# controler.net
KiCad netlist of a schematic drawn in Altium Designer
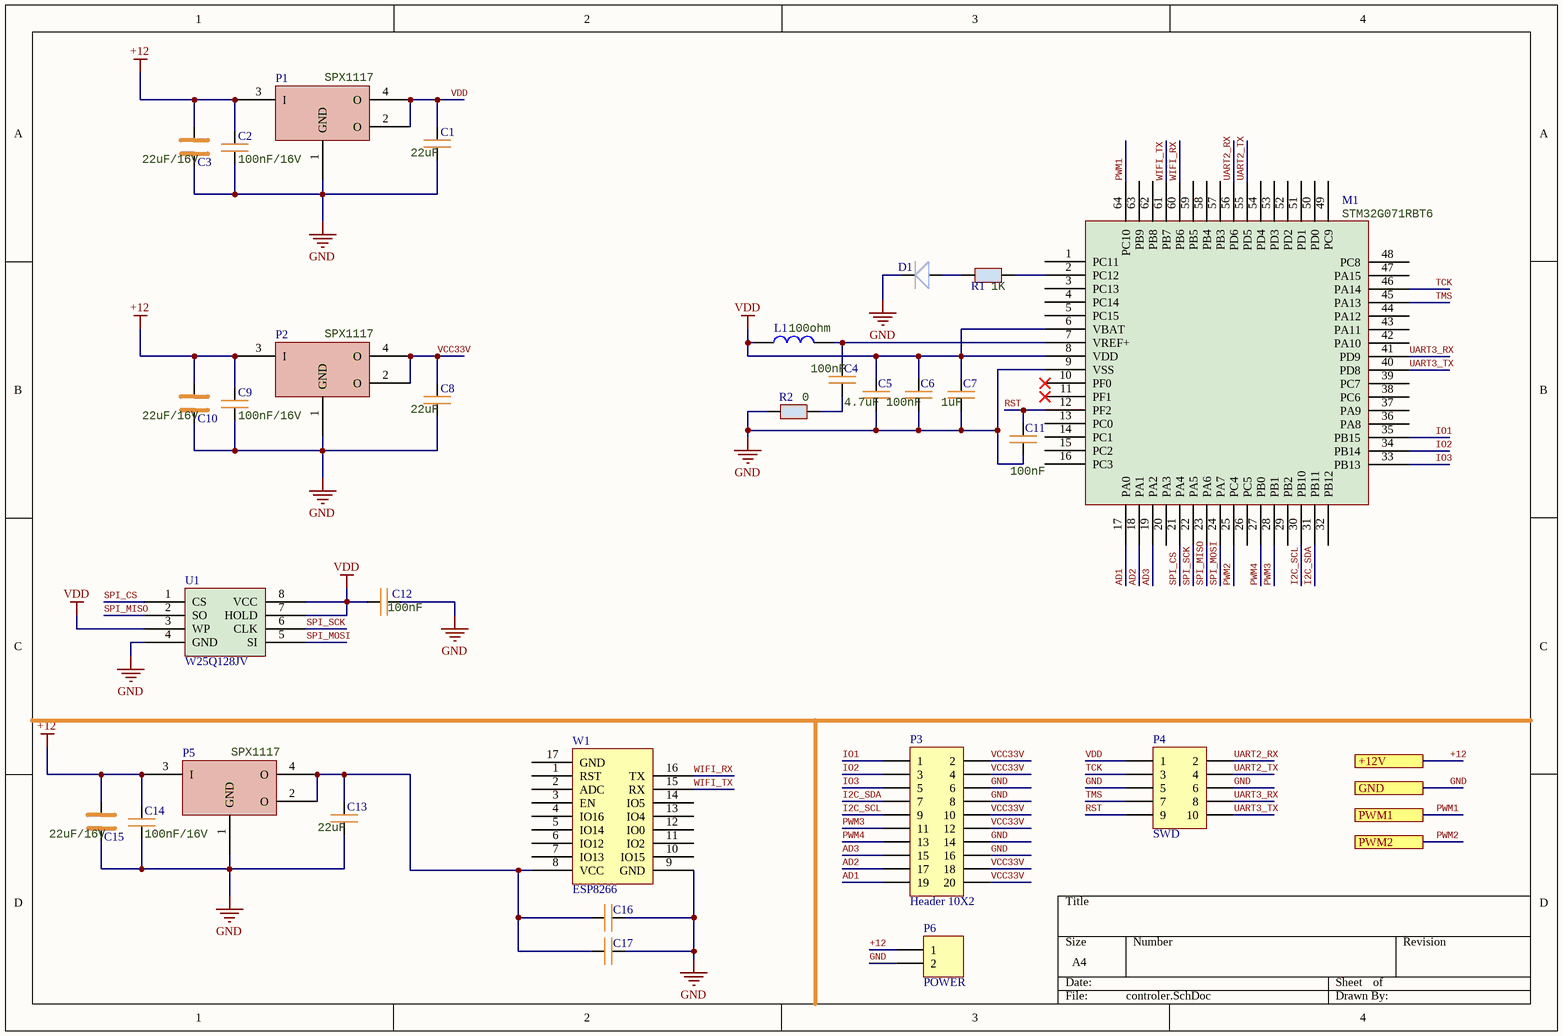
[diagram p0: controler.SchDoc]

(export (version "E")
  (design (tool "Eeschema 10.0.6"))
  (components
    (comp (ref "C1")
      (value "22uF")
      (footprint "CAP0603")
      (description "CAP0603")
      (libsource (lib "led2") (part "CAP0603"))
    )
    (comp (ref "C2")
      (value "100nF/16V")
      (footprint "CAP0603")
      (description "CAP0603")
      (libsource (lib "led2") (part "CAP0603"))
    )
    (comp (ref "C3")
      (value "22uF/16V")
      (footprint "cap1210")
      (description "CAP1210")
      (libsource (lib "led2") (part "CAP1210"))
    )
    (comp (ref "C4")
      (value "100nF")
      (footprint "CAP0603")
      (description "CAP0603")
      (libsource (lib "led2") (part "CAP0603"))
    )
    (comp (ref "C5")
      (value "4.7uF")
      (footprint "CAP0603")
      (description "CAP0603")
      (libsource (lib "led2") (part "CAP0603"))
    )
    (comp (ref "C6")
      (value "100nF")
      (footprint "CAP0603")
      (description "CAP0603")
      (libsource (lib "led2") (part "CAP0603"))
    )
    (comp (ref "C7")
      (value "1uF")
      (footprint "CAP0603")
      (description "CAP0603")
      (libsource (lib "led2") (part "CAP0603"))
    )
    (comp (ref "C8")
      (value "22uF")
      (footprint "CAP0603")
      (description "CAP0603")
      (libsource (lib "led2") (part "CAP0603"))
    )
    (comp (ref "C9")
      (value "100nF/16V")
      (footprint "CAP0603")
      (description "CAP0603")
      (libsource (lib "led2") (part "CAP0603"))
    )
    (comp (ref "C10")
      (value "22uF/16V")
      (footprint "cap1210")
      (description "CAP1210")
      (libsource (lib "led2") (part "CAP1210"))
    )
    (comp (ref "C11")
      (value "100nF")
      (footprint "CAP0603")
      (description "CAP0603")
      (libsource (lib "led2") (part "CAP0603"))
    )
    (comp (ref "C12")
      (value "100nF")
      (footprint "CAP0603")
      (description "CAP0603")
      (libsource (lib "led2") (part "CAP0603"))
    )
    (comp (ref "C13")
      (value "22uF")
      (footprint "CAP0603")
      (description "CAP0603")
      (libsource (lib "led2") (part "CAP0603"))
    )
    (comp (ref "C14")
      (value "100nF/16V")
      (footprint "CAP0603")
      (description "CAP0603")
      (libsource (lib "led2") (part "CAP0603"))
    )
    (comp (ref "C15")
      (value "22uF/16V")
      (footprint "cap1210")
      (description "CAP1210")
      (libsource (lib "led2") (part "CAP1210"))
    )
    (comp (ref "C16") (value "CAP0603") (footprint "CAP0603") (libsource (lib "led2") (part "CAP0603")))
    (comp (ref "C17") (value "CAP0603") (footprint "CAP0603") (libsource (lib "led2") (part "CAP0603")))
    (comp (ref "D1")
      (value "led0603")
      (footprint "led0603")
      (description "这是一个二极管")
      (libsource (lib "led2") (part "led0603"))
    )
    (comp (ref "L1")
      (value "100ohm")
      (footprint "bead0603")
      (description "a bead")
      (libsource (lib "led2") (part "bead0603"))
    )
    (comp (ref "M1")
      (value "controller")
      (footprint "STM32G071RB")
      (description "STM32G071RB")
      (fields
        (field (name "MANUFACTURER") "STMicroelectronics")
        (field (name "MANUFACTURER PART NUMBER") "STM32G071RBT6")
      )
      (libsource (lib "led2") (part "STM32G071RB"))
    )
    (comp (ref "P1")
      (value "SPX1117")
      (footprint "1117")
      (description "LDO --> 3.3")
      (libsource (lib "led2") (part "SPX1117"))
    )
    (comp (ref "P2")
      (value "SPX1117")
      (footprint "1117")
      (description "LDO --> 3.3")
      (libsource (lib "led2") (part "SPX1117"))
    )
    (comp (ref "P3")
      (value "Header 10X2")
      (footprint "HDR2X10")
      (description "Header, 10-Pin, Dual row")
      (fields (field (name "PUBLISHER") "Altium Limited"))
      (libsource (lib "Miscellaneous Connectors") (part "Header 10X2"))
    )
    (comp (ref "P4")
      (value "SWD")
      (footprint "HDR2X5")
      (description "Header, 5-Pin, Dual row")
      (fields (field (name "PUBLISHER") "Altium Limited"))
      (libsource (lib "Miscellaneous Connectors") (part "Header 5X2"))
    )
    (comp (ref "P5")
      (value "SPX1117")
      (footprint "1117")
      (description "LDO --> 3.3")
      (libsource (lib "led2") (part "SPX1117"))
    )
    (comp (ref "P6")
      (value "POWER")
      (footprint "HDR1X2")
      (description "Header, 2-Pin")
      (fields (field (name "PUBLISHER") "Altium Limited"))
      (libsource (lib "Miscellaneous Connectors") (part "Header 2"))
    )
    (comp (ref "R1")
      (value "1K")
      (footprint "res0603")
      (description "RES0603")
      (libsource (lib "led2") (part "RES0603"))
    )
    (comp (ref "R2")
      (value "0")
      (footprint "res0603")
      (description "RES0603")
      (libsource (lib "led2") (part "RES0603"))
    )
    (comp (ref "U1") (value "W25Q128JV") (footprint "W25Q128") (libsource (lib "led2") (part "W25Q128JV")))
    (comp (ref "W1") (value "ESP8266") (footprint "ESP-12S") (libsource (lib "led2") (part "ESP8266")))
  )
  (nets
    (net (code "1") (name "+12") (class "Default")
      (node (ref "C10") (pin "2") (pintype "passive"))
      (node (ref "C14") (pin "2") (pintype "passive"))
      (node (ref "C15") (pin "2") (pintype "passive"))
      (node (ref "C2") (pin "2") (pintype "passive"))
      (node (ref "C3") (pin "2") (pintype "passive"))
      (node (ref "C9") (pin "2") (pintype "passive"))
      (node (ref "P1") (pin "3") (pinfunction "I_3") (pintype "passive"))
      (node (ref "P2") (pin "3") (pinfunction "I_3") (pintype "passive"))
      (node (ref "P5") (pin "3") (pinfunction "I_3") (pintype "passive"))
      (node (ref "P6") (pin "1") (pinfunction "1_1") (pintype "passive"))
    )
    (net (code "2") (name "/AD1") (class "Default")
      (node (ref "M1") (pin "17") (pinfunction "PA0_17") (pintype "passive"))
      (node (ref "P3") (pin "19") (pinfunction "19_19") (pintype "passive"))
    )
    (net (code "3") (name "/AD2") (class "Default")
      (node (ref "M1") (pin "18") (pinfunction "PA1_18") (pintype "passive"))
      (node (ref "P3") (pin "17") (pinfunction "17_17") (pintype "passive"))
    )
    (net (code "4") (name "/AD3") (class "Default")
      (node (ref "M1") (pin "19") (pinfunction "PA2_19") (pintype "passive"))
      (node (ref "P3") (pin "15") (pinfunction "15_15") (pintype "passive"))
    )
    (net (code "5") (name "/I2C_SCL") (class "Default")
      (node (ref "M1") (pin "30") (pinfunction "PB10_30") (pintype "passive"))
      (node (ref "P3") (pin "9") (pinfunction "9_9") (pintype "passive"))
    )
    (net (code "6") (name "/I2C_SDA") (class "Default")
      (node (ref "M1") (pin "31") (pinfunction "PB11_31") (pintype "passive"))
      (node (ref "P3") (pin "7") (pinfunction "7_7") (pintype "passive"))
    )
    (net (code "7") (name "/IO1") (class "Default")
      (node (ref "M1") (pin "35") (pinfunction "PB15_35") (pintype "passive"))
      (node (ref "P3") (pin "1") (pinfunction "1_1") (pintype "passive"))
    )
    (net (code "8") (name "/IO2") (class "Default")
      (node (ref "M1") (pin "34") (pinfunction "PB14_34") (pintype "passive"))
      (node (ref "P3") (pin "3") (pinfunction "3_3") (pintype "passive"))
    )
    (net (code "9") (name "/IO3") (class "Default")
      (node (ref "M1") (pin "33") (pinfunction "PB13_33") (pintype "passive"))
      (node (ref "P3") (pin "5") (pinfunction "5_5") (pintype "passive"))
    )
    (net (code "10") (name "/PWM1") (class "Default")
      (node (ref "M1") (pin "64") (pinfunction "PC10_64") (pintype "passive"))
    )
    (net (code "11") (name "/PWM2") (class "Default")
      (node (ref "M1") (pin "25") (pinfunction "PC4_25") (pintype "passive"))
    )
    (net (code "12") (name "/PWM3") (class "Default")
      (node (ref "M1") (pin "28") (pinfunction "PB1_28") (pintype "passive"))
      (node (ref "P3") (pin "11") (pinfunction "11_11") (pintype "passive"))
    )
    (net (code "13") (name "/PWM4") (class "Default")
      (node (ref "M1") (pin "27") (pinfunction "PB0_27") (pintype "passive"))
      (node (ref "P3") (pin "13") (pinfunction "13_13") (pintype "passive"))
    )
    (net (code "14") (name "/RST") (class "Default")
      (node (ref "C11") (pin "2") (pintype "passive"))
      (node (ref "M1") (pin "12") (pinfunction "PF2_12") (pintype "passive"))
      (node (ref "P4") (pin "9") (pinfunction "9_9") (pintype "passive"))
    )
    (net (code "15") (name "/SPI_CS") (class "Default")
      (node (ref "M1") (pin "21") (pinfunction "PA4_21") (pintype "passive"))
      (node (ref "U1") (pin "1") (pinfunction "CS_1") (pintype "passive"))
    )
    (net (code "16") (name "/SPI_MISO") (class "Default")
      (node (ref "M1") (pin "23") (pinfunction "PA6_23") (pintype "passive"))
      (node (ref "U1") (pin "2") (pinfunction "SO_2") (pintype "passive"))
    )
    (net (code "17") (name "/SPI_MOSI") (class "Default")
      (node (ref "M1") (pin "24") (pinfunction "PA7_24") (pintype "passive"))
      (node (ref "U1") (pin "5") (pinfunction "SI_5") (pintype "passive"))
    )
    (net (code "18") (name "/SPI_SCK") (class "Default")
      (node (ref "M1") (pin "22") (pinfunction "PA5_22") (pintype "passive"))
      (node (ref "U1") (pin "6") (pinfunction "CLK_6") (pintype "passive"))
    )
    (net (code "19") (name "/TCK") (class "Default")
      (node (ref "M1") (pin "46") (pinfunction "PA14_46") (pintype "passive"))
      (node (ref "P4") (pin "3") (pinfunction "3_3") (pintype "passive"))
    )
    (net (code "20") (name "/TMS") (class "Default")
      (node (ref "M1") (pin "45") (pinfunction "PA13_45") (pintype "passive"))
      (node (ref "P4") (pin "7") (pinfunction "7_7") (pintype "passive"))
    )
    (net (code "21") (name "/UART2_RX") (class "Default")
      (node (ref "M1") (pin "56") (pinfunction "PD6_56") (pintype "passive"))
      (node (ref "P4") (pin "2") (pinfunction "2_2") (pintype "passive"))
    )
    (net (code "22") (name "/UART2_TX") (class "Default")
      (node (ref "M1") (pin "55") (pinfunction "PD5_55") (pintype "passive"))
      (node (ref "P4") (pin "4") (pinfunction "4_4") (pintype "passive"))
    )
    (net (code "23") (name "/UART3_RX") (class "Default")
      (node (ref "M1") (pin "41") (pinfunction "PD9_41") (pintype "passive"))
      (node (ref "P4") (pin "8") (pinfunction "8_8") (pintype "passive"))
    )
    (net (code "24") (name "/UART3_TX") (class "Default")
      (node (ref "M1") (pin "40") (pinfunction "PD8_40") (pintype "passive"))
      (node (ref "P4") (pin "10") (pinfunction "10_10") (pintype "passive"))
    )
    (net (code "25") (name "/VCC33V") (class "Default")
      (node (ref "C8") (pin "2") (pintype "passive"))
      (node (ref "P2") (pin "2") (pinfunction "O_2") (pintype "passive"))
      (node (ref "P2") (pin "4") (pinfunction "O_4") (pintype "passive"))
      (node (ref "P3") (pin "10") (pinfunction "10_10") (pintype "passive"))
      (node (ref "P3") (pin "12") (pinfunction "12_12") (pintype "passive"))
      (node (ref "P3") (pin "18") (pinfunction "18_18") (pintype "passive"))
      (node (ref "P3") (pin "2") (pinfunction "2_2") (pintype "passive"))
      (node (ref "P3") (pin "20") (pinfunction "20_20") (pintype "passive"))
      (node (ref "P3") (pin "4") (pinfunction "4_4") (pintype "passive"))
    )
    (net (code "26") (name "/WIFI_RX") (class "Default")
      (node (ref "M1") (pin "60") (pinfunction "PB6_60") (pintype "passive"))
      (node (ref "W1") (pin "16") (pinfunction "TX_16") (pintype "passive"))
    )
    (net (code "27") (name "/WIFI_TX") (class "Default")
      (node (ref "M1") (pin "61") (pinfunction "PB7_61") (pintype "passive"))
      (node (ref "W1") (pin "15") (pinfunction "RX_15") (pintype "passive"))
    )
    (net (code "28") (name "GND") (class "Default")
      (node (ref "C1") (pin "1") (pintype "passive"))
      (node (ref "C10") (pin "1") (pintype "passive"))
      (node (ref "C11") (pin "1") (pintype "passive"))
      (node (ref "C12") (pin "1") (pintype "passive"))
      (node (ref "C13") (pin "1") (pintype "passive"))
      (node (ref "C14") (pin "1") (pintype "passive"))
      (node (ref "C15") (pin "1") (pintype "passive"))
      (node (ref "C16") (pin "2") (pintype "passive"))
      (node (ref "C17") (pin "2") (pintype "passive"))
      (node (ref "C2") (pin "1") (pintype "passive"))
      (node (ref "C3") (pin "1") (pintype "passive"))
      (node (ref "C5") (pin "1") (pintype "passive"))
      (node (ref "C6") (pin "1") (pintype "passive"))
      (node (ref "C7") (pin "1") (pintype "passive"))
      (node (ref "C8") (pin "1") (pintype "passive"))
      (node (ref "C9") (pin "1") (pintype "passive"))
      (node (ref "D1") (pin "1") (pintype "passive"))
      (node (ref "M1") (pin "9") (pinfunction "VSS_9") (pintype "passive"))
      (node (ref "P1") (pin "1") (pinfunction "GND_1") (pintype "passive"))
      (node (ref "P2") (pin "1") (pinfunction "GND_1") (pintype "passive"))
      (node (ref "P3") (pin "14") (pinfunction "14_14") (pintype "passive"))
      (node (ref "P3") (pin "16") (pinfunction "16_16") (pintype "passive"))
      (node (ref "P3") (pin "6") (pinfunction "6_6") (pintype "passive"))
      (node (ref "P3") (pin "8") (pinfunction "8_8") (pintype "passive"))
      (node (ref "P4") (pin "5") (pinfunction "5_5") (pintype "passive"))
      (node (ref "P4") (pin "6") (pinfunction "6_6") (pintype "passive"))
      (node (ref "P5") (pin "1") (pinfunction "GND_1") (pintype "passive"))
      (node (ref "P6") (pin "2") (pinfunction "2_2") (pintype "passive"))
      (node (ref "R2") (pin "1") (pintype "passive"))
      (node (ref "U1") (pin "4") (pinfunction "GND_4") (pintype "passive"))
      (node (ref "W1") (pin "9") (pinfunction "GND_9") (pintype "passive"))
    )
    (net (code "29") (name "Net-(C4-Pad1)") (class "Default")
      (node (ref "C4") (pin "1") (pintype "passive"))
      (node (ref "R2") (pin "2") (pintype "passive"))
    )
    (net (code "30") (name "Net-(D1-Pad2)") (class "Default")
      (node (ref "D1") (pin "2") (pintype "passive"))
      (node (ref "R1") (pin "1") (pintype "passive"))
    )
    (net (code "31") (name "Net-(M1-PC12)") (class "Default")
      (node (ref "M1") (pin "2") (pinfunction "PC12_2") (pintype "passive"))
      (node (ref "R1") (pin "2") (pintype "passive"))
    )
    (net (code "32") (name "Net-(M1-VREF+)") (class "Default")
      (node (ref "C4") (pin "2") (pintype "passive"))
      (node (ref "L1") (pin "2") (pintype "passive"))
      (node (ref "M1") (pin "7") (pinfunction "VREF+_7") (pintype "passive"))
    )
    (net (code "33") (name "Net-(W1-VCC)") (class "Default")
      (node (ref "C13") (pin "2") (pintype "passive"))
      (node (ref "C16") (pin "1") (pintype "passive"))
      (node (ref "C17") (pin "1") (pintype "passive"))
      (node (ref "P5") (pin "2") (pinfunction "O_2") (pintype "passive"))
      (node (ref "P5") (pin "4") (pinfunction "O_4") (pintype "passive"))
      (node (ref "W1") (pin "8") (pinfunction "VCC_8") (pintype "passive"))
    )
    (net (code "34") (name "VDD") (class "Default")
      (node (ref "C1") (pin "2") (pintype "passive"))
      (node (ref "C12") (pin "2") (pintype "passive"))
      (node (ref "C5") (pin "2") (pintype "passive"))
      (node (ref "C6") (pin "2") (pintype "passive"))
      (node (ref "C7") (pin "2") (pintype "passive"))
      (node (ref "L1") (pin "1") (pintype "passive"))
      (node (ref "M1") (pin "6") (pinfunction "VBAT_6") (pintype "passive"))
      (node (ref "M1") (pin "8") (pinfunction "VDD_8") (pintype "passive"))
      (node (ref "P1") (pin "2") (pinfunction "O_2") (pintype "passive"))
      (node (ref "P1") (pin "4") (pinfunction "O_4") (pintype "passive"))
      (node (ref "P4") (pin "1") (pinfunction "1_1") (pintype "passive"))
      (node (ref "U1") (pin "3") (pinfunction "WP_3") (pintype "passive"))
      (node (ref "U1") (pin "7") (pinfunction "HOLD_7") (pintype "passive"))
      (node (ref "U1") (pin "8") (pinfunction "VCC_8") (pintype "passive"))
    )
    (net (code "35") (name "unconnected-(M1-PA3-Pad20)") (class "Default")
      (node (ref "M1") (pin "20") (pinfunction "PA3_20") (pintype "passive"))
    )
    (net (code "36") (name "unconnected-(M1-PA8-Pad36)") (class "Default")
      (node (ref "M1") (pin "36") (pinfunction "PA8_36") (pintype "passive"))
    )
    (net (code "37") (name "unconnected-(M1-PA9-Pad37)") (class "Default")
      (node (ref "M1") (pin "37") (pinfunction "PA9_37") (pintype "passive"))
    )
    (net (code "38") (name "unconnected-(M1-PA10-Pad42)") (class "Default")
      (node (ref "M1") (pin "42") (pinfunction "PA10_42") (pintype "passive"))
    )
    (net (code "39") (name "unconnected-(M1-PA11-Pad43)") (class "Default")
      (node (ref "M1") (pin "43") (pinfunction "PA11_43") (pintype "passive"))
    )
    (net (code "40") (name "unconnected-(M1-PA12-Pad44)") (class "Default")
      (node (ref "M1") (pin "44") (pinfunction "PA12_44") (pintype "passive"))
    )
    (net (code "41") (name "unconnected-(M1-PA15-Pad47)") (class "Default")
      (node (ref "M1") (pin "47") (pinfunction "PA15_47") (pintype "passive"))
    )
    (net (code "42") (name "unconnected-(M1-PB2-Pad29)") (class "Default")
      (node (ref "M1") (pin "29") (pinfunction "PB2_29") (pintype "passive"))
    )
    (net (code "43") (name "unconnected-(M1-PB3-Pad57)") (class "Default")
      (node (ref "M1") (pin "57") (pinfunction "PB3_57") (pintype "passive"))
    )
    (net (code "44") (name "unconnected-(M1-PB4-Pad58)") (class "Default")
      (node (ref "M1") (pin "58") (pinfunction "PB4_58") (pintype "passive"))
    )
    (net (code "45") (name "unconnected-(M1-PB5-Pad59)") (class "Default")
      (node (ref "M1") (pin "59") (pinfunction "PB5_59") (pintype "passive"))
    )
    (net (code "46") (name "unconnected-(M1-PB8-Pad62)") (class "Default")
      (node (ref "M1") (pin "62") (pinfunction "PB8_62") (pintype "passive"))
    )
    (net (code "47") (name "unconnected-(M1-PB9-Pad63)") (class "Default")
      (node (ref "M1") (pin "63") (pinfunction "PB9_63") (pintype "passive"))
    )
    (net (code "48") (name "unconnected-(M1-PB12-Pad32)") (class "Default")
      (node (ref "M1") (pin "32") (pinfunction "PB12_32") (pintype "passive"))
    )
    (net (code "49") (name "unconnected-(M1-PC0-Pad13)") (class "Default")
      (node (ref "M1") (pin "13") (pinfunction "PC0_13") (pintype "passive"))
    )
    (net (code "50") (name "unconnected-(M1-PC1-Pad14)") (class "Default")
      (node (ref "M1") (pin "14") (pinfunction "PC1_14") (pintype "passive"))
    )
    (net (code "51") (name "unconnected-(M1-PC2-Pad15)") (class "Default")
      (node (ref "M1") (pin "15") (pinfunction "PC2_15") (pintype "passive"))
    )
    (net (code "52") (name "unconnected-(M1-PC3-Pad16)") (class "Default")
      (node (ref "M1") (pin "16") (pinfunction "PC3_16") (pintype "passive"))
    )
    (net (code "53") (name "unconnected-(M1-PC5-Pad26)") (class "Default")
      (node (ref "M1") (pin "26") (pinfunction "PC5_26") (pintype "passive"))
    )
    (net (code "54") (name "unconnected-(M1-PC6-Pad38)") (class "Default")
      (node (ref "M1") (pin "38") (pinfunction "PC6_38") (pintype "passive"))
    )
    (net (code "55") (name "unconnected-(M1-PC7-Pad39)") (class "Default")
      (node (ref "M1") (pin "39") (pinfunction "PC7_39") (pintype "passive"))
    )
    (net (code "56") (name "unconnected-(M1-PC8-Pad48)") (class "Default")
      (node (ref "M1") (pin "48") (pinfunction "PC8_48") (pintype "passive"))
    )
    (net (code "57") (name "unconnected-(M1-PC9-Pad49)") (class "Default")
      (node (ref "M1") (pin "49") (pinfunction "PC9_49") (pintype "passive"))
    )
    (net (code "58") (name "unconnected-(M1-PC11-Pad1)") (class "Default")
      (node (ref "M1") (pin "1") (pinfunction "PC11_1") (pintype "passive"))
    )
    (net (code "59") (name "unconnected-(M1-PC13-Pad3)") (class "Default")
      (node (ref "M1") (pin "3") (pinfunction "PC13_3") (pintype "passive"))
    )
    (net (code "60") (name "unconnected-(M1-PC14-Pad4)") (class "Default")
      (node (ref "M1") (pin "4") (pinfunction "PC14_4") (pintype "passive"))
    )
    (net (code "61") (name "unconnected-(M1-PC15-Pad5)") (class "Default")
      (node (ref "M1") (pin "5") (pinfunction "PC15_5") (pintype "passive"))
    )
    (net (code "62") (name "unconnected-(M1-PD0-Pad50)") (class "Default")
      (node (ref "M1") (pin "50") (pinfunction "PD0_50") (pintype "passive"))
    )
    (net (code "63") (name "unconnected-(M1-PD1-Pad51)") (class "Default")
      (node (ref "M1") (pin "51") (pinfunction "PD1_51") (pintype "passive"))
    )
    (net (code "64") (name "unconnected-(M1-PD2-Pad52)") (class "Default")
      (node (ref "M1") (pin "52") (pinfunction "PD2_52") (pintype "passive"))
    )
    (net (code "65") (name "unconnected-(M1-PD3-Pad53)") (class "Default")
      (node (ref "M1") (pin "53") (pinfunction "PD3_53") (pintype "passive"))
    )
    (net (code "66") (name "unconnected-(M1-PD4-Pad54)") (class "Default")
      (node (ref "M1") (pin "54") (pinfunction "PD4_54") (pintype "passive"))
    )
    (net (code "67") (name "unconnected-(M1-PF0-Pad10)") (class "Default")
      (node (ref "M1") (pin "10") (pinfunction "PF0_10") (pintype "passive+no_connect"))
    )
    (net (code "68") (name "unconnected-(M1-PF1-Pad11)") (class "Default")
      (node (ref "M1") (pin "11") (pinfunction "PF1_11") (pintype "passive+no_connect"))
    )
    (net (code "69") (name "unconnected-(W1-ADC-Pad2)") (class "Default")
      (node (ref "W1") (pin "2") (pinfunction "ADC_2") (pintype "passive"))
    )
    (net (code "70") (name "unconnected-(W1-EN-Pad3)") (class "Default")
      (node (ref "W1") (pin "3") (pinfunction "EN_3") (pintype "passive"))
    )
    (net (code "71") (name "unconnected-(W1-GND-Pad17)") (class "Default")
      (node (ref "W1") (pin "17") (pinfunction "GND_17") (pintype "passive"))
    )
    (net (code "72") (name "unconnected-(W1-IO0-Pad12)") (class "Default")
      (node (ref "W1") (pin "12") (pinfunction "IO0_12") (pintype "passive"))
    )
    (net (code "73") (name "unconnected-(W1-IO2-Pad11)") (class "Default")
      (node (ref "W1") (pin "11") (pinfunction "IO2_11") (pintype "passive"))
    )
    (net (code "74") (name "unconnected-(W1-IO4-Pad13)") (class "Default")
      (node (ref "W1") (pin "13") (pinfunction "IO4_13") (pintype "passive"))
    )
    (net (code "75") (name "unconnected-(W1-IO5-Pad14)") (class "Default")
      (node (ref "W1") (pin "14") (pinfunction "IO5_14") (pintype "passive"))
    )
    (net (code "76") (name "unconnected-(W1-IO12-Pad6)") (class "Default")
      (node (ref "W1") (pin "6") (pinfunction "IO12_6") (pintype "passive"))
    )
    (net (code "77") (name "unconnected-(W1-IO13-Pad7)") (class "Default")
      (node (ref "W1") (pin "7") (pinfunction "IO13_7") (pintype "passive"))
    )
    (net (code "78") (name "unconnected-(W1-IO14-Pad5)") (class "Default")
      (node (ref "W1") (pin "5") (pinfunction "IO14_5") (pintype "passive"))
    )
    (net (code "79") (name "unconnected-(W1-IO15-Pad10)") (class "Default")
      (node (ref "W1") (pin "10") (pinfunction "IO15_10") (pintype "passive"))
    )
    (net (code "80") (name "unconnected-(W1-IO16-Pad4)") (class "Default")
      (node (ref "W1") (pin "4") (pinfunction "IO16_4") (pintype "passive"))
    )
    (net (code "81") (name "unconnected-(W1-RST-Pad1)") (class "Default")
      (node (ref "W1") (pin "1") (pinfunction "RST_1") (pintype "passive"))
    )
  )
)
